# Power_schematic.net
KiCad netlist of a schematic drawn in Altium Designer
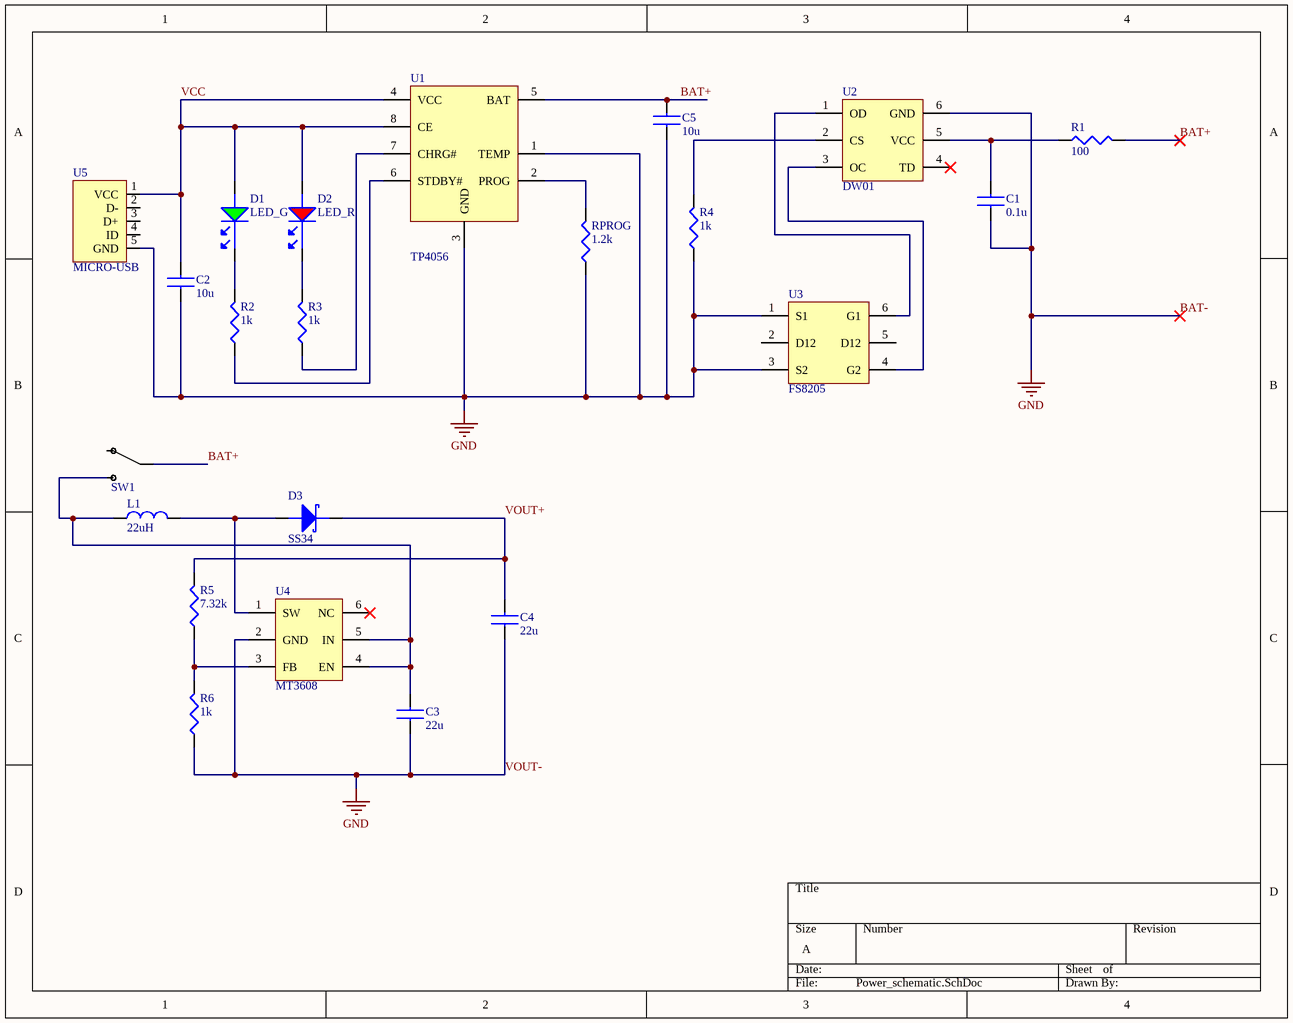
[diagram p0: Power_schematic.SchDoc]

(export (version "E")
  (design (tool "Eeschema 10.0.6"))
  (components
    (comp (ref "C1")
      (value "0.1u")
      (footprint "CL03")
      (description "Cap Ceramic 0.1uF 6.3VDC X5R 10% SMD 0201 Paper T/R")
      (fields
        (field (name "MANUFACTURER") "Samsung")
        (field (name "MANUFACTURER PART NUMBER") "CL03A104KQ3NNNC")
      )
      (libsource (lib "Power_Schlib1") (part "478-5052-1-ND"))
    )
    (comp (ref "C2")
      (value "10u")
      (footprint "CL21")
      (description "Cap Ceramic 10uF 6.3V X5R 10% SMD 0805 85C Embossed T/R")
      (fields
        (field (name "MANUFACTURER") "Samsung")
        (field (name "MANUFACTURER PART NUMBER") "CL21A106KQFNNNE")
      )
      (libsource (lib "Power_Schlib1") (part "CL21A106KQFNNNE"))
    )
    (comp (ref "C3")
      (value "22u")
      (footprint "CL10")
      (description "Cap Ceramic 22uF 6.3V X5R 20% SMD 0603 85°C Cardboard T/R")
      (fields
        (field (name "MANUFACTURER") "Samsung")
        (field (name "MANUFACTURER PART NUMBER") "CL10A226MQ8NRNC")
      )
      (libsource (lib "Power_Schlib1") (part "1276-1013-1-ND"))
    )
    (comp (ref "C4")
      (value "22u")
      (footprint "CL10")
      (description "Cap Ceramic 22uF 6.3V X5R 20% SMD 0603 85°C Cardboard T/R")
      (fields
        (field (name "MANUFACTURER") "Samsung")
        (field (name "MANUFACTURER PART NUMBER") "CL10A226MQ8NRNC")
      )
      (libsource (lib "Power_Schlib1") (part "1276-1013-1-ND"))
    )
    (comp (ref "C5")
      (value "10u")
      (footprint "CL21")
      (description "Cap Ceramic 10uF 6.3V X5R 10% SMD 0805 85C Embossed T/R")
      (fields
        (field (name "MANUFACTURER") "Samsung")
        (field (name "MANUFACTURER PART NUMBER") "CL21A106KQFNNNE")
      )
      (libsource (lib "Power_Schlib1") (part "CL21A106KQFNNNE"))
    )
    (comp (ref "D1")
      (value "LED_G")
      (footprint "SML-E12")
      (description "LED Uni-Color Yellow Green 2-Pin Chip LED T/R")
      (fields (field (name "MANUFACTURER") "Rohm") (field (name "MANUFACTURER PART NUMBER") "SML-E12M8WT86"))
      (libsource (lib "Power_Schlib1") (part "SML-E12M8WT86"))
    )
    (comp (ref "D2")
      (value "LED_R")
      (footprint "SML-E12")
      (description "ROHM - SML-E12U8WT86 - LED, Rosso, SMD, 603, 20 mA, 2.2 V, 620 nm")
      (fields (field (name "MANUFACTURER") "Rohm") (field (name "MANUFACTURER PART NUMBER") "SML-E12U8WT86"))
      (libsource (lib "Power_Schlib1") (part "SML-E12U8WT86"))
    )
    (comp (ref "D3")
      (value "SS34")
      (footprint "SS34")
      (description "DIODE SCHOTTKY 40V 3A SMC")
      (fields (field (name "MANUFACTURER") "ON Semiconductor / Fairchild") (field (name "VOLTAGE") "40V"))
      (libsource (lib "Power_Schlib1") (part "SS34"))
    )
    (comp (ref "L1")
      (value "22uH")
      (footprint "CBC3225")
      (description "Inductor Power Chip Wirewound 22uH 20% 100KHz Ferrite 0.62A 0.351Ohm DCR 1210 T/R")
      (fields
        (field (name "MANUFACTURER") "Taiyo Yuden")
        (field (name "MANUFACTURER PART NUMBER") "CBC3225T220MR")
      )
      (libsource (lib "Power_Schlib1") (part "CBC3225T220MR"))
    )
    (comp (ref "R1")
      (value "100")
      (footprint "RMCP2010")
      (description "RES 100 OHM 1W 5% 2010")
      (fields
        (field (name "MANUFACTURER") "Stackpole Electronics")
        (field (name "MANUFACTURER PART NUMBER") "RMCP2010JT100R")
      )
      (libsource (lib "Power_Schlib1") (part "RMCP2010JT100R"))
    )
    (comp (ref "R2")
      (value "1k")
      (footprint "RMCP2512")
      (description "Res Thick Film 2512 1K Ohm 5% 1W ±200ppm/°C Molded SMD Plastic T/R")
      (fields
        (field (name "MANUFACTURER") "Stackpole Electronics")
        (field (name "MANUFACTURER PART NUMBER") "RMCF2512JT1K00")
      )
      (libsource (lib "Power_Schlib1") (part "RMCF2512JT1K00"))
    )
    (comp (ref "R3")
      (value "1k")
      (footprint "RMCP2512")
      (description "Res Thick Film 2512 1K Ohm 5% 1W ±200ppm/°C Molded SMD Plastic T/R")
      (fields
        (field (name "MANUFACTURER") "Stackpole Electronics")
        (field (name "MANUFACTURER PART NUMBER") "RMCF2512JT1K00")
      )
      (libsource (lib "Power_Schlib1") (part "RMCF2512JT1K00"))
    )
    (comp (ref "R4")
      (value "1k")
      (footprint "RMCP2512")
      (description "Res Thick Film 2512 1K Ohm 5% 1W ±200ppm/°C Molded SMD Plastic T/R")
      (fields
        (field (name "MANUFACTURER") "Stackpole Electronics")
        (field (name "MANUFACTURER PART NUMBER") "RMCF2512JT1K00")
      )
      (libsource (lib "Power_Schlib1") (part "RMCF2512JT1K00"))
    )
    (comp (ref "R5")
      (value "7.32k")
      (footprint "RMCP1206")
      (description "RES SMD 7.32K OHM 1% 1/4W 1206")
      (fields
        (field (name "MANUFACTURER") "Stackpole Electronics")
        (field (name "MANUFACTURER PART NUMBER") "RMCF1206FT7K32")
      )
      (libsource (lib "Power_Schlib1") (part "RMCF1206FT7K32"))
    )
    (comp (ref "R6")
      (value "1k")
      (footprint "RMCP2512")
      (description "Res Thick Film 2512 1K Ohm 5% 1W ±200ppm/°C Molded SMD Plastic T/R")
      (fields
        (field (name "MANUFACTURER") "Stackpole Electronics")
        (field (name "MANUFACTURER PART NUMBER") "RMCF2512JT1K00")
      )
      (libsource (lib "Power_Schlib1") (part "RMCF2512JT1K00"))
    )
    (comp (ref "RPROG")
      (value "1.2k")
      (footprint "RMCP2512")
      (description "Res Thick Film 2512 1.2K Ohm 5% 1W 100ppm/C Molded SMD SMD Plastic T/R")
      (fields
        (field (name "MANUFACTURER") "Stackpole Electronics")
        (field (name "MANUFACTURER PART NUMBER") "RMCF2512JT1K20")
      )
      (libsource (lib "Power_Schlib1") (part "RMCF2512JT1K20"))
    )
    (comp (ref "SW1") (value "SW") (footprint "SWITCH") (libsource (lib "Power_Schlib1") (part "Switch")))
    (comp (ref "U1") (value "TP4056") (footprint "TP4056") (libsource (lib "Power_Schlib1") (part "TP4056")))
    (comp (ref "U2") (value "DW01") (footprint "DW01") (libsource (lib "Power_Schlib1") (part "DW01")))
    (comp (ref "U3") (value "FS8205") (footprint "FS8205") (libsource (lib "Power_Schlib1") (part "FS8205")))
    (comp (ref "U4") (value "MT3608") (footprint "MT3608") (libsource (lib "Power_Schlib1") (part "MT3608")))
    (comp (ref "U5")
      (value "MICRO-USB")
      (footprint "USB")
      (description "Micro A/b Skt, Bottom-smt, R/a, 3")
      (fields
        (field (name "MANUFACTURER") "Global Connector Technology")
        (field (name "MANUFACTURER PART NUMBER") "USB3090-30-A")
      )
      (libsource (lib "Power_Schlib1") (part "USB3090-30-A"))
    )
  )
  (nets
    (net (code "1") (name "/BAT+") (class "Default")
      (node (ref "C5") (pin "2") (pinfunction "7_2") (pintype "passive"))
      (node (ref "R1") (pin "2") (pinfunction "2_2") (pintype "passive"))
      (node (ref "SW1") (pin "2") (pinfunction "5_2") (pintype "passive"))
      (node (ref "U1") (pin "5") (pinfunction "BAT_5") (pintype "passive"))
    )
    (net (code "2") (name "/VCC") (class "Default")
      (node (ref "C2") (pin "2") (pinfunction "7_2") (pintype "passive"))
      (node (ref "D1") (pin "2") (pinfunction "2_2") (pintype "passive"))
      (node (ref "D2") (pin "2") (pinfunction "2_2") (pintype "passive"))
      (node (ref "U1") (pin "4") (pinfunction "VCC_4") (pintype "passive"))
      (node (ref "U1") (pin "8") (pinfunction "CE_8") (pintype "passive"))
      (node (ref "U5") (pin "1") (pinfunction "VCC_1") (pintype "passive"))
    )
    (net (code "3") (name "/VOUT+") (class "Default")
      (node (ref "C4") (pin "2") (pinfunction "7_2") (pintype "passive"))
      (node (ref "D3") (pin "K") (pinfunction "15_K") (pintype "passive"))
      (node (ref "R5") (pin "2") (pinfunction "2_2") (pintype "passive"))
    )
    (net (code "4") (name "GND") (class "Default")
      (node (ref "C1") (pin "1") (pinfunction "6_1") (pintype "passive"))
      (node (ref "C2") (pin "1") (pinfunction "6_1") (pintype "passive"))
      (node (ref "C3") (pin "1") (pinfunction "6_1") (pintype "passive"))
      (node (ref "C4") (pin "1") (pinfunction "6_1") (pintype "passive"))
      (node (ref "C5") (pin "1") (pinfunction "6_1") (pintype "passive"))
      (node (ref "R4") (pin "1") (pinfunction "1_1") (pintype "passive"))
      (node (ref "R6") (pin "1") (pinfunction "1_1") (pintype "passive"))
      (node (ref "RPROG") (pin "1") (pinfunction "1_1") (pintype "passive"))
      (node (ref "U1") (pin "1") (pinfunction "TEMP_1") (pintype "passive"))
      (node (ref "U1") (pin "3") (pinfunction "GND_3") (pintype "passive"))
      (node (ref "U2") (pin "6") (pinfunction "GND_6") (pintype "passive"))
      (node (ref "U3") (pin "1") (pinfunction "S1_1") (pintype "passive"))
      (node (ref "U3") (pin "3") (pinfunction "S2_3") (pintype "passive"))
      (node (ref "U4") (pin "2") (pinfunction "GND_2") (pintype "passive"))
      (node (ref "U5") (pin "5") (pinfunction "GND_5") (pintype "passive"))
    )
    (net (code "5") (name "Net-(C1-7)") (class "Default")
      (node (ref "C1") (pin "2") (pinfunction "7_2") (pintype "passive"))
      (node (ref "R1") (pin "1") (pinfunction "1_1") (pintype "passive"))
      (node (ref "U2") (pin "5") (pinfunction "VCC_5") (pintype "passive"))
    )
    (net (code "6") (name "Net-(C3-7)") (class "Default")
      (node (ref "C3") (pin "2") (pinfunction "7_2") (pintype "passive"))
      (node (ref "L1") (pin "1") (pinfunction "1_1") (pintype "passive"))
      (node (ref "SW1") (pin "3") (pinfunction "6_3") (pintype "passive"))
      (node (ref "U4") (pin "4") (pinfunction "EN_4") (pintype "passive"))
      (node (ref "U4") (pin "5") (pinfunction "IN_5") (pintype "passive"))
    )
    (net (code "7") (name "Net-(D1-Pad1)") (class "Default")
      (node (ref "D1") (pin "1") (pinfunction "1_1") (pintype "passive"))
      (node (ref "R2") (pin "2") (pinfunction "2_2") (pintype "passive"))
    )
    (net (code "8") (name "Net-(D2-Pad1)") (class "Default")
      (node (ref "D2") (pin "1") (pinfunction "1_1") (pintype "passive"))
      (node (ref "R3") (pin "2") (pinfunction "2_2") (pintype "passive"))
    )
    (net (code "9") (name "Net-(D3-14)") (class "Default")
      (node (ref "D3") (pin "A") (pinfunction "14_A") (pintype "passive"))
      (node (ref "L1") (pin "2") (pinfunction "2_2") (pintype "passive"))
      (node (ref "U4") (pin "1") (pinfunction "SW_1") (pintype "passive"))
    )
    (net (code "10") (name "Net-(U1-CHRG#)") (class "Default")
      (node (ref "R3") (pin "1") (pinfunction "1_1") (pintype "passive"))
      (node (ref "U1") (pin "7") (pinfunction "CHRG#_7") (pintype "passive"))
    )
    (net (code "11") (name "Net-(U1-PROG)") (class "Default")
      (node (ref "RPROG") (pin "2") (pinfunction "2_2") (pintype "passive"))
      (node (ref "U1") (pin "2") (pinfunction "PROG_2") (pintype "passive"))
    )
    (net (code "12") (name "Net-(U1-STDBY#)") (class "Default")
      (node (ref "R2") (pin "1") (pinfunction "1_1") (pintype "passive"))
      (node (ref "U1") (pin "6") (pinfunction "STDBY#_6") (pintype "passive"))
    )
    (net (code "13") (name "Net-(U2-CS)") (class "Default")
      (node (ref "R4") (pin "2") (pinfunction "2_2") (pintype "passive"))
      (node (ref "U2") (pin "2") (pinfunction "CS_2") (pintype "passive"))
    )
    (net (code "14") (name "Net-(U2-OC)") (class "Default")
      (node (ref "U2") (pin "3") (pinfunction "OC_3") (pintype "passive"))
      (node (ref "U3") (pin "4") (pinfunction "G2_4") (pintype "passive"))
    )
    (net (code "15") (name "Net-(U2-OD)") (class "Default")
      (node (ref "U2") (pin "1") (pinfunction "OD_1") (pintype "passive"))
      (node (ref "U3") (pin "6") (pinfunction "G1_6") (pintype "passive"))
    )
    (net (code "16") (name "Net-(U4-FB)") (class "Default")
      (node (ref "R5") (pin "1") (pinfunction "1_1") (pintype "passive"))
      (node (ref "R6") (pin "2") (pinfunction "2_2") (pintype "passive"))
      (node (ref "U4") (pin "3") (pinfunction "FB_3") (pintype "passive"))
    )
    (net (code "17") (name "unconnected-(SW1-7-Pad1)") (class "Default")
      (node (ref "SW1") (pin "1") (pinfunction "7_1") (pintype "passive"))
    )
    (net (code "18") (name "unconnected-(U2-TD-Pad4)") (class "Default")
      (node (ref "U2") (pin "4") (pinfunction "TD_4") (pintype "passive+no_connect"))
    )
    (net (code "19") (name "unconnected-(U3-D12-Pad2)") (class "Default")
      (node (ref "U3") (pin "2") (pinfunction "D12_2") (pintype "passive"))
    )
    (net (code "20") (name "unconnected-(U3-D12-Pad5)") (class "Default")
      (node (ref "U3") (pin "5") (pinfunction "D12_5") (pintype "passive"))
    )
    (net (code "21") (name "unconnected-(U4-NC-Pad6)") (class "Default")
      (node (ref "U4") (pin "6") (pinfunction "NC_6") (pintype "passive+no_connect"))
    )
    (net (code "22") (name "unconnected-(U5-D+-Pad3)") (class "Default")
      (node (ref "U5") (pin "3") (pinfunction "D+_3") (pintype "passive"))
    )
    (net (code "23") (name "unconnected-(U5-D--Pad2)") (class "Default")
      (node (ref "U5") (pin "2") (pinfunction "D-_2") (pintype "passive"))
    )
    (net (code "24") (name "unconnected-(U5-ID-Pad4)") (class "Default")
      (node (ref "U5") (pin "4") (pinfunction "ID_4") (pintype "passive"))
    )
  )
)
